# design.net
KiCad netlist of a schematic drawn in Altium Designer
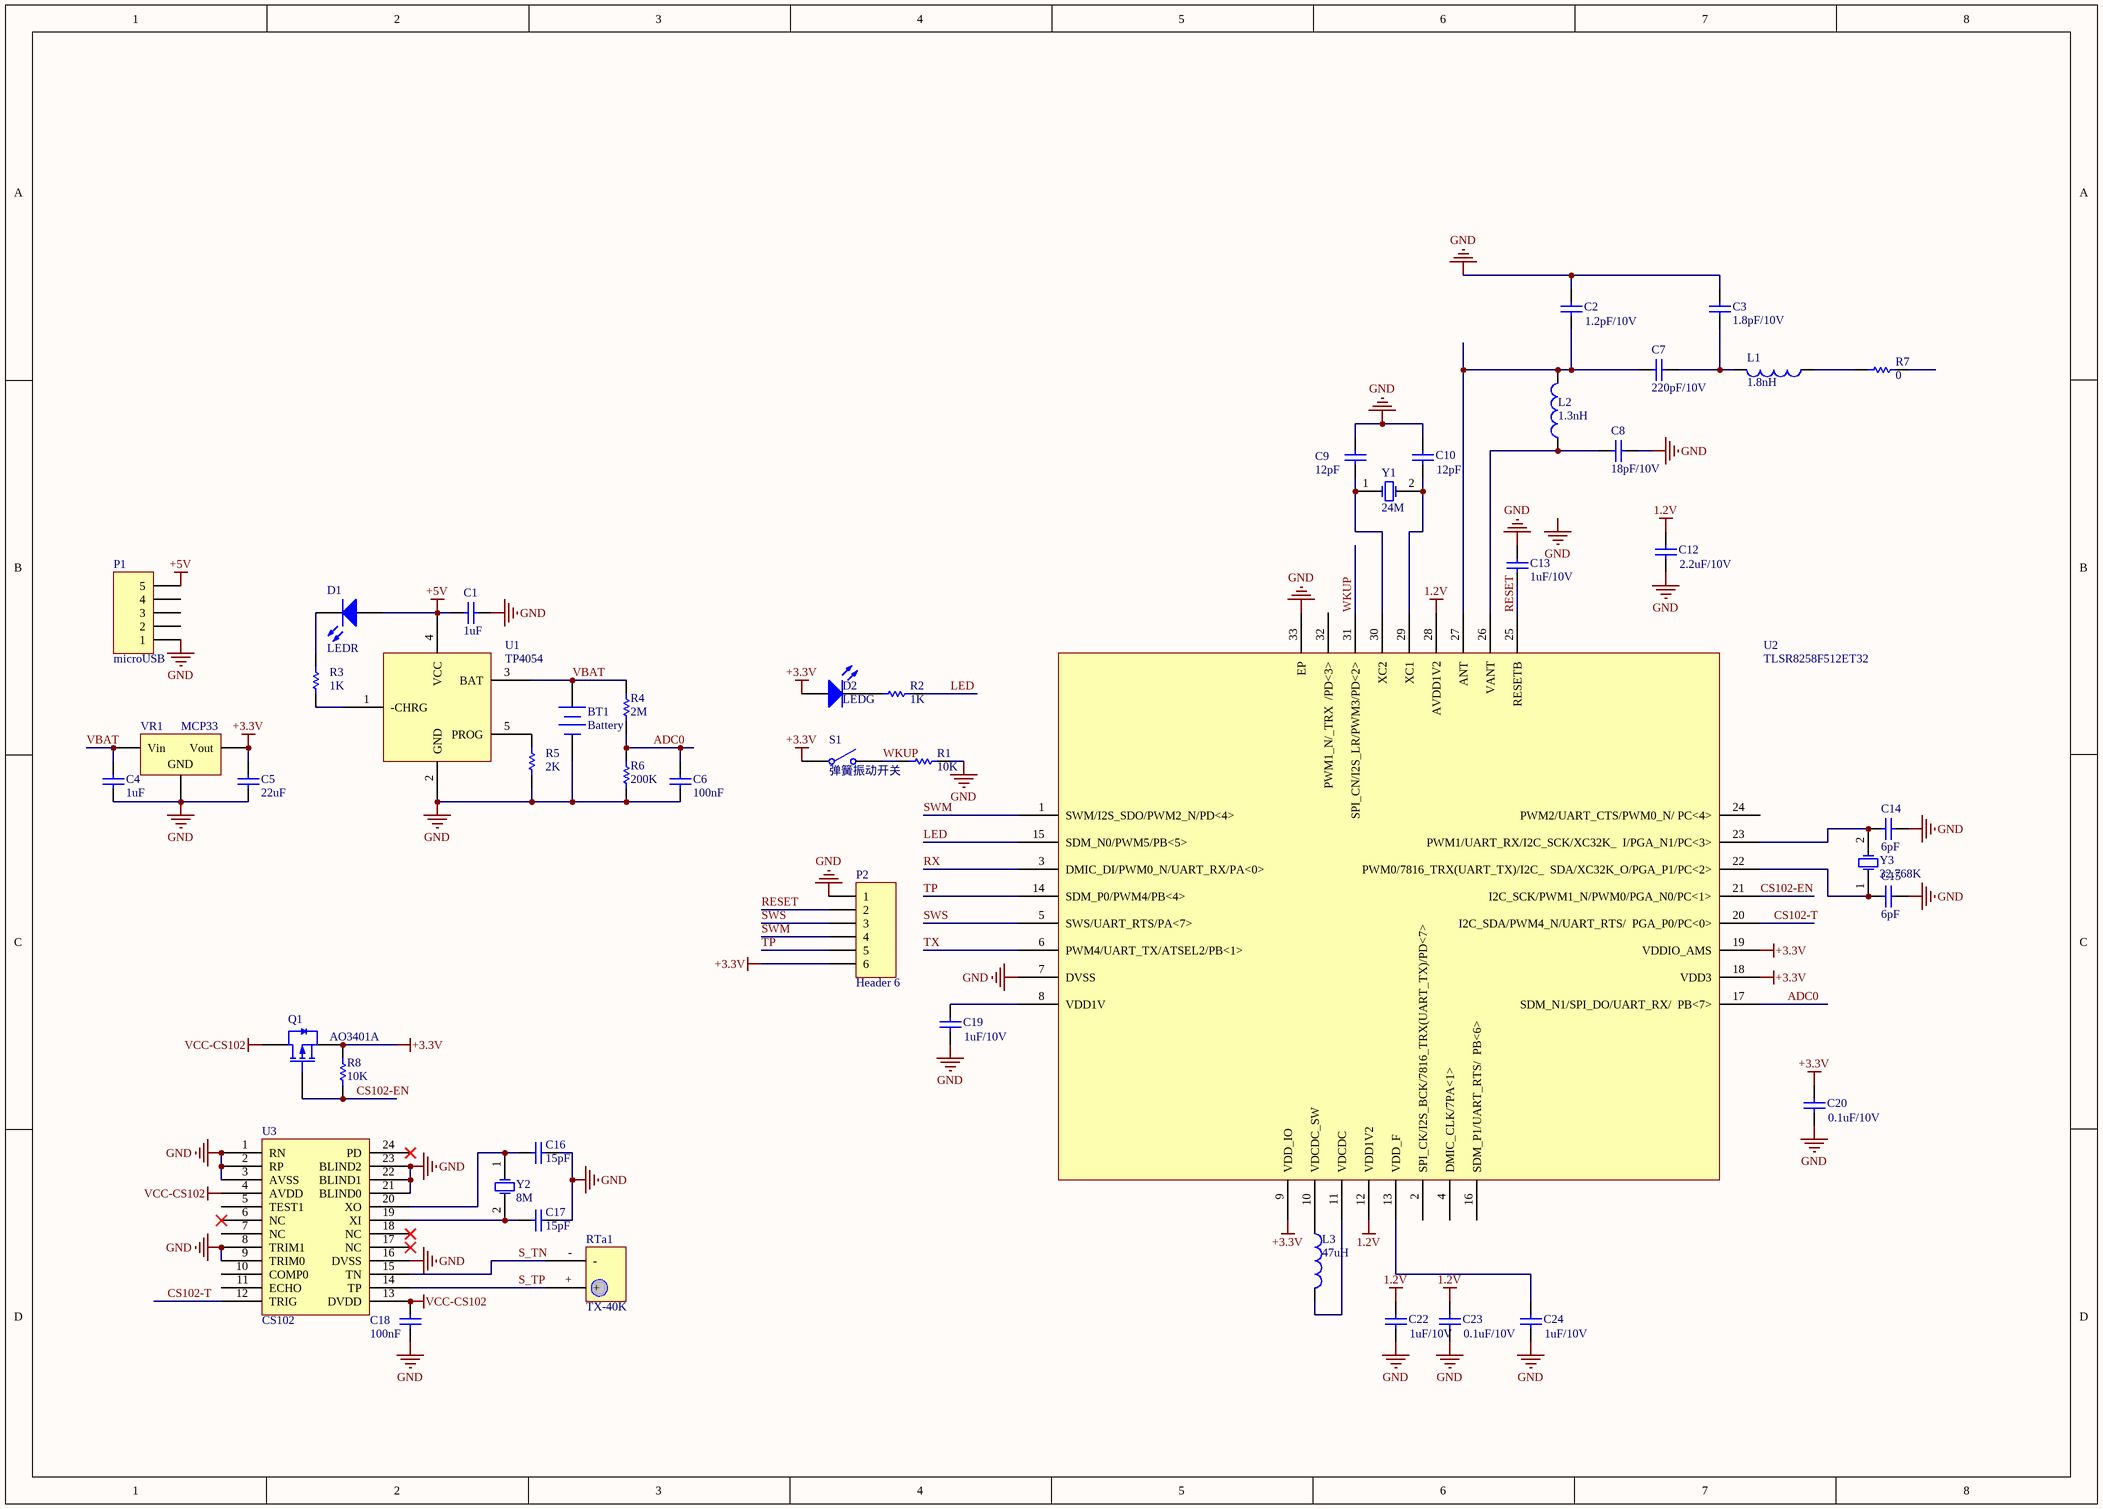
[diagram p0: 发送端原理图.SchDoc]

(export (version "E")
  (design (tool "Eeschema 10.0.6"))
  (components
    (comp (ref "BT1")
      (value "Battery")
      (footprint "BT")
      (description "Multicell Battery")
      (fields (field (name "PUBLISHER") "Altium Limited"))
      (libsource (lib "Miscellaneous Devices") (part "Battery"))
    )
    (comp (ref "C1")
      (value "1uF")
      (description "Capacitor")
      (fields (field (name "PUBLISHER") "Altium Limited"))
      (libsource (lib "Miscellaneous Devices") (part "Cap"))
    )
    (comp (ref "C2")
      (value "1.2pF/10V")
      (footprint "0402")
      (description "Capacitor")
      (fields (field (name "PUBLISHER") "Altium Limited"))
      (libsource (lib "Miscellaneous Devices") (part "Cap"))
    )
    (comp (ref "C3")
      (value "1.8pF/10V")
      (footprint "0402")
      (description "Capacitor")
      (fields (field (name "PUBLISHER") "Altium Limited"))
      (libsource (lib "Miscellaneous Devices") (part "Cap"))
    )
    (comp (ref "C4")
      (value "1uF")
      (description "Capacitor")
      (fields (field (name "PUBLISHER") "Altium Limited"))
      (libsource (lib "Miscellaneous Devices") (part "Cap"))
    )
    (comp (ref "C5")
      (value "22uF")
      (description "Capacitor")
      (fields (field (name "PUBLISHER") "Altium Limited"))
      (libsource (lib "Miscellaneous Devices") (part "Cap"))
    )
    (comp (ref "C6")
      (value "100nF")
      (description "Capacitor")
      (fields (field (name "PUBLISHER") "Altium Limited"))
      (libsource (lib "Miscellaneous Devices") (part "Cap"))
    )
    (comp (ref "C7")
      (value "220pF/10V")
      (footprint "0402")
      (description "Capacitor")
      (fields (field (name "PUBLISHER") "Altium Limited"))
      (libsource (lib "Miscellaneous Devices") (part "Cap"))
    )
    (comp (ref "C8")
      (value "18pF/10V")
      (footprint "0402")
      (description "Capacitor")
      (fields (field (name "PUBLISHER") "Altium Limited"))
      (libsource (lib "Miscellaneous Devices") (part "Cap"))
    )
    (comp (ref "C9")
      (value "12pF")
      (footprint "0402")
      (description "Capacitor")
      (fields (field (name "PUBLISHER") "Altium Limited"))
      (libsource (lib "Miscellaneous Devices") (part "Cap"))
    )
    (comp (ref "C10")
      (value "12pF")
      (footprint "0402")
      (description "Capacitor")
      (fields (field (name "PUBLISHER") "Altium Limited"))
      (libsource (lib "Miscellaneous Devices") (part "Cap"))
    )
    (comp (ref "C12")
      (value "2.2uF/10V")
      (footprint "0402")
      (description "Capacitor")
      (fields (field (name "PUBLISHER") "Altium Limited"))
      (libsource (lib "Miscellaneous Devices") (part "Cap"))
    )
    (comp (ref "C13")
      (value "1uF/10V")
      (footprint "0402")
      (description "Capacitor")
      (fields (field (name "PUBLISHER") "Altium Limited"))
      (libsource (lib "Miscellaneous Devices") (part "Cap"))
    )
    (comp (ref "C14")
      (value "6pF")
      (footprint "0402")
      (description "Capacitor")
      (fields (field (name "PUBLISHER") "Altium Limited"))
      (libsource (lib "Miscellaneous Devices") (part "Cap"))
    )
    (comp (ref "C15")
      (value "6pF")
      (footprint "0402")
      (description "Capacitor")
      (fields (field (name "PUBLISHER") "Altium Limited"))
      (libsource (lib "Miscellaneous Devices") (part "Cap"))
    )
    (comp (ref "C16")
      (value "15pF")
      (footprint "0402")
      (description "Capacitor")
      (fields (field (name "PUBLISHER") "Altium Limited"))
      (libsource (lib "Miscellaneous Devices") (part "Cap"))
    )
    (comp (ref "C17")
      (value "15pF")
      (footprint "0402")
      (description "Capacitor")
      (fields (field (name "PUBLISHER") "Altium Limited"))
      (libsource (lib "Miscellaneous Devices") (part "Cap"))
    )
    (comp (ref "C18")
      (value "100nF")
      (description "Capacitor")
      (fields (field (name "PUBLISHER") "Altium Limited"))
      (libsource (lib "Miscellaneous Devices") (part "Cap"))
    )
    (comp (ref "C19")
      (value "1uF/10V")
      (footprint "0402")
      (description "Capacitor")
      (fields (field (name "PUBLISHER") "Altium Limited"))
      (libsource (lib "Miscellaneous Devices") (part "Cap"))
    )
    (comp (ref "C20")
      (value "0.1uF/10V")
      (footprint "0402")
      (description "Capacitor")
      (fields (field (name "PUBLISHER") "Altium Limited"))
      (libsource (lib "Miscellaneous Devices") (part "Cap"))
    )
    (comp (ref "C22")
      (value "1uF/10V")
      (footprint "0402")
      (description "Capacitor")
      (fields (field (name "PUBLISHER") "Altium Limited"))
      (libsource (lib "Miscellaneous Devices") (part "Cap"))
    )
    (comp (ref "C23")
      (value "0.1uF/10V")
      (footprint "0402")
      (description "Capacitor")
      (fields (field (name "PUBLISHER") "Altium Limited"))
      (libsource (lib "Miscellaneous Devices") (part "Cap"))
    )
    (comp (ref "C24")
      (value "1uF/10V")
      (footprint "0402")
      (description "Capacitor")
      (fields (field (name "PUBLISHER") "Altium Limited"))
      (libsource (lib "Miscellaneous Devices") (part "Cap"))
    )
    (comp (ref "D1")
      (value "LEDR")
      (footprint "LED0603")
      (description "Typical INFRARED GaAs LED")
      (fields (field (name "PUBLISHER") "Altium Limited"))
      (libsource (lib "Miscellaneous Devices") (part "LED0"))
    )
    (comp (ref "D2")
      (value "LEDG")
      (footprint "LED0603")
      (description "Typical INFRARED GaAs LED")
      (fields (field (name "PUBLISHER") "Altium Limited"))
      (libsource (lib "Miscellaneous Devices") (part "LED0"))
    )
    (comp (ref "L1")
      (value "1.8nH")
      (description "Inductor")
      (fields (field (name "PUBLISHER") "Altium Limited"))
      (libsource (lib "Miscellaneous Devices") (part "Inductor"))
    )
    (comp (ref "L2")
      (value "1.3nH")
      (description "Inductor")
      (fields (field (name "PUBLISHER") "Altium Limited"))
      (libsource (lib "Miscellaneous Devices") (part "Inductor"))
    )
    (comp (ref "L3")
      (value "47uH")
      (footprint "0603R")
      (description "Inductor")
      (fields (field (name "PUBLISHER") "Altium Limited"))
      (libsource (lib "Miscellaneous Devices") (part "Inductor"))
    )
    (comp (ref "P1")
      (value "microUSB")
      (footprint "MICROUSB")
      (description "Header, 5-Pin")
      (fields (field (name "PUBLISHER") "Altium Limited"))
      (libsource (lib "Miscellaneous Connectors") (part "Header 5"))
    )
    (comp (ref "P2")
      (value "Header 6")
      (footprint "SIP6-1.27")
      (description "Header, 6-Pin")
      (fields (field (name "PUBLISHER") "Altium Limited"))
      (libsource (lib "Miscellaneous Connectors") (part "Header 6"))
    )
    (comp (ref "Q1")
      (value "AO3401A")
      (footprint "AO3401")
      (description "MOS(场效应管)")
      (libsource (lib "Miscellaneous Devices LC") (part "AO3401A P道沟 X13A15 SOT-23"))
    )
    (comp (ref "R1")
      (value "10K")
      (description "Resistor")
      (fields (field (name "PUBLISHER") "Altium Limited"))
      (libsource (lib "Miscellaneous Devices") (part "Res1"))
    )
    (comp (ref "R2")
      (value "1K")
      (description "Resistor")
      (fields (field (name "PUBLISHER") "Altium Limited"))
      (libsource (lib "Miscellaneous Devices") (part "Res1"))
    )
    (comp (ref "R3")
      (value "1K")
      (description "Resistor")
      (fields (field (name "PUBLISHER") "Altium Limited"))
      (libsource (lib "Miscellaneous Devices") (part "Res1"))
    )
    (comp (ref "R4")
      (value "2M")
      (description "Resistor")
      (fields (field (name "PUBLISHER") "Altium Limited"))
      (libsource (lib "Miscellaneous Devices") (part "Res1"))
    )
    (comp (ref "R5")
      (value "2K")
      (description "Resistor")
      (fields (field (name "PUBLISHER") "Altium Limited"))
      (libsource (lib "Miscellaneous Devices") (part "Res1"))
    )
    (comp (ref "R6")
      (value "200K")
      (description "Resistor")
      (fields (field (name "PUBLISHER") "Altium Limited"))
      (libsource (lib "Miscellaneous Devices") (part "Res1"))
    )
    (comp (ref "R7")
      (value "0")
      (description "Resistor")
      (fields (field (name "PUBLISHER") "Altium Limited"))
      (libsource (lib "Miscellaneous Devices") (part "Res1"))
    )
    (comp (ref "R8")
      (value "10K")
      (description "Resistor")
      (fields (field (name "PUBLISHER") "Altium Limited"))
      (libsource (lib "Miscellaneous Devices") (part "Res1"))
    )
    (comp (ref "RTa1") (value "TX-40K") (footprint "US-10mm") (libsource (lib "USLib") (part "TC40K")))
    (comp (ref "S1")
      (value "弹簧振动开关")
      (footprint "SW")
      (description "Single-Pole, Single-Throw Switch")
      (fields (field (name "PUBLISHER") "Altium Limited"))
      (libsource (lib "Miscellaneous Devices") (part "SW-SPST"))
    )
    (comp (ref "U1") (value "TP4054") (footprint "TP4054") (libsource (lib "Schlib1") (part "TP4054")))
    (comp (ref "U2")
      (value "TLSR8258F512ET32")
      (footprint "QFN-32")
      (libsource (lib "stm32") (part "TLSR8258F512ET32"))
    )
    (comp (ref "U3") (value "CS102") (footprint "TSSOP24") (libsource (lib "USLib") (part "CS100")))
    (comp (ref "VR1")
      (value "MCP33")
      (footprint "MCP33")
      (description "Voltage Regulator")
      (fields (field (name "PUBLISHER") "Altium Limited"))
      (libsource (lib "Miscellaneous Devices") (part "Volt Reg"))
    )
    (comp (ref "Y1")
      (value "24M")
      (footprint "XTAL4TN_3225")
      (description "Crystal Oscillator")
      (fields (field (name "PUBLISHER") "Altium Limited"))
      (libsource (lib "Miscellaneous Devices") (part "XTAL"))
    )
    (comp (ref "Y2")
      (value "8M")
      (footprint "5032")
      (description "Crystal Oscillator")
      (fields (field (name "PUBLISHER") "Altium Limited"))
      (libsource (lib "Miscellaneous Devices") (part "XTAL"))
    )
    (comp (ref "Y3")
      (value "32.768K")
      (footprint "XTAL3215")
      (description "Crystal Oscillator")
      (fields (field (name "PUBLISHER") "Altium Limited"))
      (libsource (lib "Miscellaneous Devices") (part "XTAL"))
    )
  )
  (nets
    (net (code "1") (name "+3.3V") (class "Default")
      (node (ref "C20") (pin "2") (pinfunction "2_2") (pintype "passive"))
      (node (ref "C5") (pin "1") (pinfunction "1_1") (pintype "passive"))
      (node (ref "D2") (pin "1") (pinfunction "A_1") (pintype "passive"))
      (node (ref "P2") (pin "6") (pinfunction "6_6") (pintype "passive"))
      (node (ref "Q1") (pin "2") (pinfunction "S_2") (pintype "passive"))
      (node (ref "R8") (pin "2") (pinfunction "2_2") (pintype "passive"))
      (node (ref "S1") (pin "1") (pinfunction "COMMON_1") (pintype "passive"))
      (node (ref "U2") (pin "18") (pinfunction "VDD3_18") (pintype "passive"))
      (node (ref "U2") (pin "19") (pinfunction "VDDIO_AMS_19") (pintype "passive"))
      (node (ref "U2") (pin "9") (pinfunction "VDD_IO_9") (pintype "passive"))
      (node (ref "VR1") (pin "3") (pinfunction "Vout_3") (pintype "passive"))
    )
    (net (code "2") (name "+5V") (class "Default")
      (node (ref "C1") (pin "2") (pinfunction "2_2") (pintype "passive"))
      (node (ref "D1") (pin "1") (pinfunction "A_1") (pintype "passive"))
      (node (ref "P1") (pin "5") (pinfunction "5_5") (pintype "passive"))
      (node (ref "U1") (pin "4") (pinfunction "VCC_4") (pintype "passive"))
    )
    (net (code "3") (name "/ADC0") (class "Default")
      (node (ref "C6") (pin "2") (pinfunction "2_2") (pintype "passive"))
      (node (ref "R4") (pin "1") (pinfunction "1_1") (pintype "passive"))
      (node (ref "R6") (pin "2") (pinfunction "2_2") (pintype "passive"))
      (node (ref "U2") (pin "17") (pinfunction "SDM_N1/SPI_DO/UART_RX/__PB<7>_17") (pintype "passive"))
    )
    (net (code "4") (name "/CS102-EN") (class "Default")
      (node (ref "Q1") (pin "1") (pinfunction "G_1") (pintype "passive"))
      (node (ref "R8") (pin "1") (pinfunction "1_1") (pintype "passive"))
      (node (ref "U2") (pin "21") (pinfunction "I2C_SCK/PWM1_N/PWM0/PGA_N0/PC<1>_21") (pintype "passive"))
    )
    (net (code "5") (name "/CS102-T") (class "Default")
      (node (ref "U2") (pin "20") (pinfunction "I2C_SDA/PWM4_N/UART_RTS/__PGA_P0/PC<0>_20") (pintype "passive"))
      (node (ref "U3") (pin "12") (pinfunction "TRIG_12") (pintype "passive"))
    )
    (net (code "6") (name "/LED") (class "Default")
      (node (ref "R2") (pin "1") (pinfunction "1_1") (pintype "passive"))
      (node (ref "U2") (pin "15") (pinfunction "SDM_N0/PWM5/PB<5>_15") (pintype "passive"))
    )
    (net (code "7") (name "/RESET") (class "Default")
      (node (ref "C13") (pin "2") (pinfunction "2_2") (pintype "passive"))
      (node (ref "P2") (pin "2") (pinfunction "2_2") (pintype "passive"))
      (node (ref "U2") (pin "25") (pinfunction "RESETB_25") (pintype "passive"))
    )
    (net (code "8") (name "/RX") (class "Default")
      (node (ref "U2") (pin "3") (pinfunction "DMIC_DI/PWM0_N/UART_RX/PA<0>_3") (pintype "passive"))
    )
    (net (code "9") (name "/SWM") (class "Default")
      (node (ref "P2") (pin "4") (pinfunction "4_4") (pintype "passive"))
      (node (ref "U2") (pin "1") (pinfunction "SWM/I2S_SDO/PWM2_N/PD<4>_1") (pintype "passive"))
    )
    (net (code "10") (name "/SWS") (class "Default")
      (node (ref "P2") (pin "3") (pinfunction "3_3") (pintype "passive"))
      (node (ref "U2") (pin "5") (pinfunction "SWS/UART_RTS/PA<7>_5") (pintype "passive"))
    )
    (net (code "11") (name "/S_TN") (class "Default")
      (node (ref "RTa1") (pin "-") (pinfunction "-_-") (pintype "passive"))
      (node (ref "U3") (pin "15") (pinfunction "TN_15") (pintype "passive"))
    )
    (net (code "12") (name "/S_TP") (class "Default")
      (node (ref "RTa1") (pin "+") (pinfunction "+_+") (pintype "passive"))
      (node (ref "U3") (pin "14") (pinfunction "TP_14") (pintype "passive"))
    )
    (net (code "13") (name "/TP") (class "Default")
      (node (ref "P2") (pin "5") (pinfunction "5_5") (pintype "passive"))
      (node (ref "U2") (pin "14") (pinfunction "SDM_P0/PWM4/PB<4>_14") (pintype "passive"))
    )
    (net (code "14") (name "/TX") (class "Default")
      (node (ref "U2") (pin "6") (pinfunction "PWM4/UART_TX/ATSEL2/PB<1>_6") (pintype "passive"))
    )
    (net (code "15") (name "/VBAT") (class "Default")
      (node (ref "BT1") (pin "1") (pinfunction "+_1") (pintype "passive"))
      (node (ref "C4") (pin "1") (pinfunction "1_1") (pintype "passive"))
      (node (ref "R4") (pin "2") (pinfunction "2_2") (pintype "passive"))
      (node (ref "U1") (pin "3") (pinfunction "BAT_3") (pintype "passive"))
      (node (ref "VR1") (pin "1") (pinfunction "Vin_1") (pintype "passive"))
    )
    (net (code "16") (name "/WKUP") (class "Default")
      (node (ref "R1") (pin "2") (pinfunction "2_2") (pintype "passive"))
      (node (ref "S1") (pin "2") (pinfunction "NO_2") (pintype "passive"))
      (node (ref "U2") (pin "31") (pinfunction "SPI_CN/I2S_LR/PWM3/PD<2>_31") (pintype "passive"))
    )
    (net (code "17") (name "1.2V") (class "Default")
      (node (ref "C12") (pin "2") (pinfunction "2_2") (pintype "passive"))
      (node (ref "C22") (pin "2") (pinfunction "2_2") (pintype "passive"))
      (node (ref "C23") (pin "2") (pinfunction "2_2") (pintype "passive"))
      (node (ref "U2") (pin "12") (pinfunction "VDD1V2_12") (pintype "passive"))
      (node (ref "U2") (pin "28") (pinfunction "AVDD1V2_28") (pintype "passive"))
    )
    (net (code "18") (name "GND") (class "Default")
      (node (ref "BT1") (pin "2") (pinfunction "-_2") (pintype "passive"))
      (node (ref "C1") (pin "1") (pinfunction "1_1") (pintype "passive"))
      (node (ref "C10") (pin "2") (pinfunction "2_2") (pintype "passive"))
      (node (ref "C12") (pin "1") (pinfunction "1_1") (pintype "passive"))
      (node (ref "C13") (pin "1") (pinfunction "1_1") (pintype "passive"))
      (node (ref "C14") (pin "1") (pinfunction "1_1") (pintype "passive"))
      (node (ref "C15") (pin "1") (pinfunction "1_1") (pintype "passive"))
      (node (ref "C16") (pin "2") (pinfunction "2_2") (pintype "passive"))
      (node (ref "C17") (pin "2") (pinfunction "2_2") (pintype "passive"))
      (node (ref "C18") (pin "1") (pinfunction "1_1") (pintype "passive"))
      (node (ref "C19") (pin "1") (pinfunction "1_1") (pintype "passive"))
      (node (ref "C2") (pin "2") (pinfunction "2_2") (pintype "passive"))
      (node (ref "C20") (pin "1") (pinfunction "1_1") (pintype "passive"))
      (node (ref "C22") (pin "1") (pinfunction "1_1") (pintype "passive"))
      (node (ref "C23") (pin "1") (pinfunction "1_1") (pintype "passive"))
      (node (ref "C24") (pin "1") (pinfunction "1_1") (pintype "passive"))
      (node (ref "C3") (pin "1") (pinfunction "1_1") (pintype "passive"))
      (node (ref "C4") (pin "2") (pinfunction "2_2") (pintype "passive"))
      (node (ref "C5") (pin "2") (pinfunction "2_2") (pintype "passive"))
      (node (ref "C6") (pin "1") (pinfunction "1_1") (pintype "passive"))
      (node (ref "C8") (pin "1") (pinfunction "1_1") (pintype "passive"))
      (node (ref "C9") (pin "2") (pinfunction "2_2") (pintype "passive"))
      (node (ref "P1") (pin "1") (pinfunction "1_1") (pintype "passive"))
      (node (ref "P2") (pin "1") (pinfunction "1_1") (pintype "passive"))
      (node (ref "R1") (pin "1") (pinfunction "1_1") (pintype "passive"))
      (node (ref "R5") (pin "1") (pinfunction "1_1") (pintype "passive"))
      (node (ref "R6") (pin "1") (pinfunction "1_1") (pintype "passive"))
      (node (ref "U1") (pin "2") (pinfunction "GND_2") (pintype "passive"))
      (node (ref "U2") (pin "33") (pinfunction "EP_33") (pintype "passive"))
      (node (ref "U2") (pin "7") (pinfunction "DVSS_7") (pintype "passive"))
      (node (ref "U3") (pin "1") (pinfunction "RN_1") (pintype "passive"))
      (node (ref "U3") (pin "16") (pinfunction "DVSS_16") (pintype "passive"))
      (node (ref "U3") (pin "2") (pinfunction "RP_2") (pintype "passive"))
      (node (ref "U3") (pin "21") (pinfunction "BLIND0_21") (pintype "passive"))
      (node (ref "U3") (pin "22") (pinfunction "BLIND1_22") (pintype "passive"))
      (node (ref "U3") (pin "23") (pinfunction "BLIND2_23") (pintype "passive"))
      (node (ref "U3") (pin "3") (pinfunction "AVSS_3") (pintype "passive"))
      (node (ref "U3") (pin "8") (pinfunction "TRIM1_8") (pintype "passive"))
      (node (ref "U3") (pin "9") (pinfunction "TRIM0_9") (pintype "passive"))
      (node (ref "VR1") (pin "2") (pinfunction "GND_2") (pintype "passive"))
    )
    (net (code "19") (name "Net-(C3-Pad2)") (class "Default")
      (node (ref "C3") (pin "2") (pinfunction "2_2") (pintype "passive"))
      (node (ref "C7") (pin "1") (pinfunction "1_1") (pintype "passive"))
      (node (ref "L1") (pin "2") (pinfunction "2_2") (pintype "passive"))
    )
    (net (code "20") (name "Net-(D1-K)") (class "Default")
      (node (ref "D1") (pin "2") (pinfunction "K_2") (pintype "passive"))
      (node (ref "R3") (pin "2") (pinfunction "2_2") (pintype "passive"))
    )
    (net (code "21") (name "Net-(D2-K)") (class "Default")
      (node (ref "D2") (pin "2") (pinfunction "K_2") (pintype "passive"))
      (node (ref "R2") (pin "2") (pinfunction "2_2") (pintype "passive"))
    )
    (net (code "22") (name "Net-(L1-Pad1)") (class "Default")
      (node (ref "L1") (pin "1") (pinfunction "1_1") (pintype "passive"))
      (node (ref "R7") (pin "2") (pinfunction "2_2") (pintype "passive"))
    )
    (net (code "23") (name "Net-(U1--CHRG)") (class "Default")
      (node (ref "R3") (pin "1") (pinfunction "1_1") (pintype "passive"))
      (node (ref "U1") (pin "1") (pinfunction "-CHRG_1") (pintype "passive"))
    )
    (net (code "24") (name "Net-(U1-PROG)") (class "Default")
      (node (ref "R5") (pin "2") (pinfunction "2_2") (pintype "passive"))
      (node (ref "U1") (pin "5") (pinfunction "PROG_5") (pintype "passive"))
    )
    (net (code "25") (name "Net-(U2-ANT)") (class "Default")
      (node (ref "C2") (pin "1") (pinfunction "1_1") (pintype "passive"))
      (node (ref "C7") (pin "2") (pinfunction "2_2") (pintype "passive"))
      (node (ref "L2") (pin "2") (pinfunction "2_2") (pintype "passive"))
      (node (ref "U2") (pin "27") (pinfunction "ANT_27") (pintype "passive"))
    )
    (net (code "26") (name "Net-(U2-PWM0{slash}7816_TRX(UART_TX){slash}I2C___SDA{slash}XC32K_O{slash}PGA_P1{slash}PC<2>)") (class "Default")
      (node (ref "C15") (pin "2") (pinfunction "2_2") (pintype "passive"))
      (node (ref "U2") (pin "22") (pinfunction "PWM0/7816_TRX(UART_TX)/I2C___SDA/XC32K_O/PGA_P1/PC<2>_22") (pintype "passive"))
      (node (ref "Y3") (pin "1") (pinfunction "OSC1_1") (pintype "passive"))
    )
    (net (code "27") (name "Net-(U2-PWM1{slash}UART_RX{slash}I2C_SCK{slash}XC32K___I{slash}PGA_N1{slash}PC<3>)") (class "Default")
      (node (ref "C14") (pin "2") (pinfunction "2_2") (pintype "passive"))
      (node (ref "U2") (pin "23") (pinfunction "PWM1/UART_RX/I2C_SCK/XC32K___I/PGA_N1/PC<3>_23") (pintype "passive"))
      (node (ref "Y3") (pin "2") (pinfunction "OSC2_2") (pintype "passive"))
    )
    (net (code "28") (name "Net-(U2-VANT)") (class "Default")
      (node (ref "C8") (pin "2") (pinfunction "2_2") (pintype "passive"))
      (node (ref "L2") (pin "1") (pinfunction "1_1") (pintype "passive"))
      (node (ref "U2") (pin "26") (pinfunction "VANT_26") (pintype "passive"))
    )
    (net (code "29") (name "Net-(U2-VDCDC)") (class "Default")
      (node (ref "L3") (pin "2") (pinfunction "2_2") (pintype "passive"))
      (node (ref "U2") (pin "11") (pinfunction "VDCDC_11") (pintype "passive"))
    )
    (net (code "30") (name "Net-(U2-VDCDC_SW)") (class "Default")
      (node (ref "L3") (pin "1") (pinfunction "1_1") (pintype "passive"))
      (node (ref "U2") (pin "10") (pinfunction "VDCDC_SW_10") (pintype "passive"))
    )
    (net (code "31") (name "Net-(U2-VDD1V)") (class "Default")
      (node (ref "C19") (pin "2") (pinfunction "2_2") (pintype "passive"))
      (node (ref "U2") (pin "8") (pinfunction "VDD1V_8") (pintype "passive"))
    )
    (net (code "32") (name "Net-(U2-VDD_F)") (class "Default")
      (node (ref "C24") (pin "2") (pinfunction "2_2") (pintype "passive"))
      (node (ref "U2") (pin "13") (pinfunction "VDD_F_13") (pintype "passive"))
    )
    (net (code "33") (name "Net-(U2-XC1)") (class "Default")
      (node (ref "C10") (pin "1") (pinfunction "1_1") (pintype "passive"))
      (node (ref "U2") (pin "29") (pinfunction "XC1_29") (pintype "passive"))
      (node (ref "Y1") (pin "2") (pinfunction "OSC2_2") (pintype "passive"))
    )
    (net (code "34") (name "Net-(U2-XC2)") (class "Default")
      (node (ref "C9") (pin "1") (pinfunction "1_1") (pintype "passive"))
      (node (ref "U2") (pin "30") (pinfunction "XC2_30") (pintype "passive"))
      (node (ref "Y1") (pin "1") (pinfunction "OSC1_1") (pintype "passive"))
    )
    (net (code "35") (name "Net-(U3-XI)") (class "Default")
      (node (ref "C17") (pin "1") (pinfunction "1_1") (pintype "passive"))
      (node (ref "U3") (pin "19") (pinfunction "XI_19") (pintype "passive"))
      (node (ref "Y2") (pin "2") (pinfunction "OSC2_2") (pintype "passive"))
    )
    (net (code "36") (name "Net-(U3-XO)") (class "Default")
      (node (ref "C16") (pin "1") (pinfunction "1_1") (pintype "passive"))
      (node (ref "U3") (pin "20") (pinfunction "XO_20") (pintype "passive"))
      (node (ref "Y2") (pin "1") (pinfunction "OSC1_1") (pintype "passive"))
    )
    (net (code "37") (name "VCC-CS102") (class "Default")
      (node (ref "C18") (pin "2") (pinfunction "2_2") (pintype "passive"))
      (node (ref "Q1") (pin "3") (pinfunction "D_3") (pintype "passive"))
      (node (ref "U3") (pin "13") (pinfunction "DVDD_13") (pintype "passive"))
      (node (ref "U3") (pin "4") (pinfunction "AVDD_4") (pintype "passive"))
    )
    (net (code "38") (name "unconnected-(P1-Pad2)") (class "Default")
      (node (ref "P1") (pin "2") (pinfunction "2_2") (pintype "passive"))
    )
    (net (code "39") (name "unconnected-(P1-Pad3)") (class "Default")
      (node (ref "P1") (pin "3") (pinfunction "3_3") (pintype "passive"))
    )
    (net (code "40") (name "unconnected-(P1-Pad4)") (class "Default")
      (node (ref "P1") (pin "4") (pinfunction "4_4") (pintype "passive"))
    )
    (net (code "41") (name "unconnected-(R7-Pad1)") (class "Default")
      (node (ref "R7") (pin "1") (pinfunction "1_1") (pintype "passive"))
    )
    (net (code "42") (name "unconnected-(U2-DMIC_CLK{slash}7PA<1>-Pad4)") (class "Default")
      (node (ref "U2") (pin "4") (pinfunction "DMIC_CLK/7PA<1>_4") (pintype "passive"))
    )
    (net (code "43") (name "unconnected-(U2-PWM1_N{slash}_TRX__{slash}PD<3>-Pad32)") (class "Default")
      (node (ref "U2") (pin "32") (pinfunction "PWM1_N/_TRX__/PD<3>_32") (pintype "passive"))
    )
    (net (code "44") (name "unconnected-(U2-PWM2{slash}UART_CTS{slash}PWM0_N{slash}_PC<4>-Pad24)") (class "Default")
      (node (ref "U2") (pin "24") (pinfunction "PWM2/UART_CTS/PWM0_N/_PC<4>_24") (pintype "passive"))
    )
    (net (code "45") (name "unconnected-(U2-SDM_P1{slash}UART_RTS{slash}__PB<6>-Pad16)") (class "Default")
      (node (ref "U2") (pin "16") (pinfunction "SDM_P1/UART_RTS/__PB<6>_16") (pintype "passive"))
    )
    (net (code "46") (name "unconnected-(U2-SPI_CK{slash}I2S_BCK{slash}7816_TRX(UART_TX){slash}PD<7>-Pad2)") (class "Default")
      (node (ref "U2") (pin "2") (pinfunction "SPI_CK/I2S_BCK/7816_TRX(UART_TX)/PD<7>_2") (pintype "passive"))
    )
    (net (code "47") (name "unconnected-(U3-COMP0-Pad10)") (class "Default")
      (node (ref "U3") (pin "10") (pinfunction "COMP0_10") (pintype "passive"))
    )
    (net (code "48") (name "unconnected-(U3-ECHO-Pad11)") (class "Default")
      (node (ref "U3") (pin "11") (pinfunction "ECHO_11") (pintype "passive"))
    )
    (net (code "49") (name "unconnected-(U3-NC-Pad6)") (class "Default")
      (node (ref "U3") (pin "6") (pinfunction "NC_6") (pintype "passive+no_connect"))
    )
    (net (code "50") (name "unconnected-(U3-NC-Pad7)") (class "Default")
      (node (ref "U3") (pin "7") (pinfunction "NC_7") (pintype "passive"))
    )
    (net (code "51") (name "unconnected-(U3-NC-Pad17)") (class "Default")
      (node (ref "U3") (pin "17") (pinfunction "NC_17") (pintype "passive+no_connect"))
    )
    (net (code "52") (name "unconnected-(U3-NC-Pad18)") (class "Default")
      (node (ref "U3") (pin "18") (pinfunction "NC_18") (pintype "passive+no_connect"))
    )
    (net (code "53") (name "unconnected-(U3-PD-Pad24)") (class "Default")
      (node (ref "U3") (pin "24") (pinfunction "PD_24") (pintype "passive+no_connect"))
    )
    (net (code "54") (name "unconnected-(U3-TEST1-Pad5)") (class "Default")
      (node (ref "U3") (pin "5") (pinfunction "TEST1_5") (pintype "passive"))
    )
  )
)
